# RPi-GPIO-V4.net
KiCad netlist of a schematic drawn in EAGLE
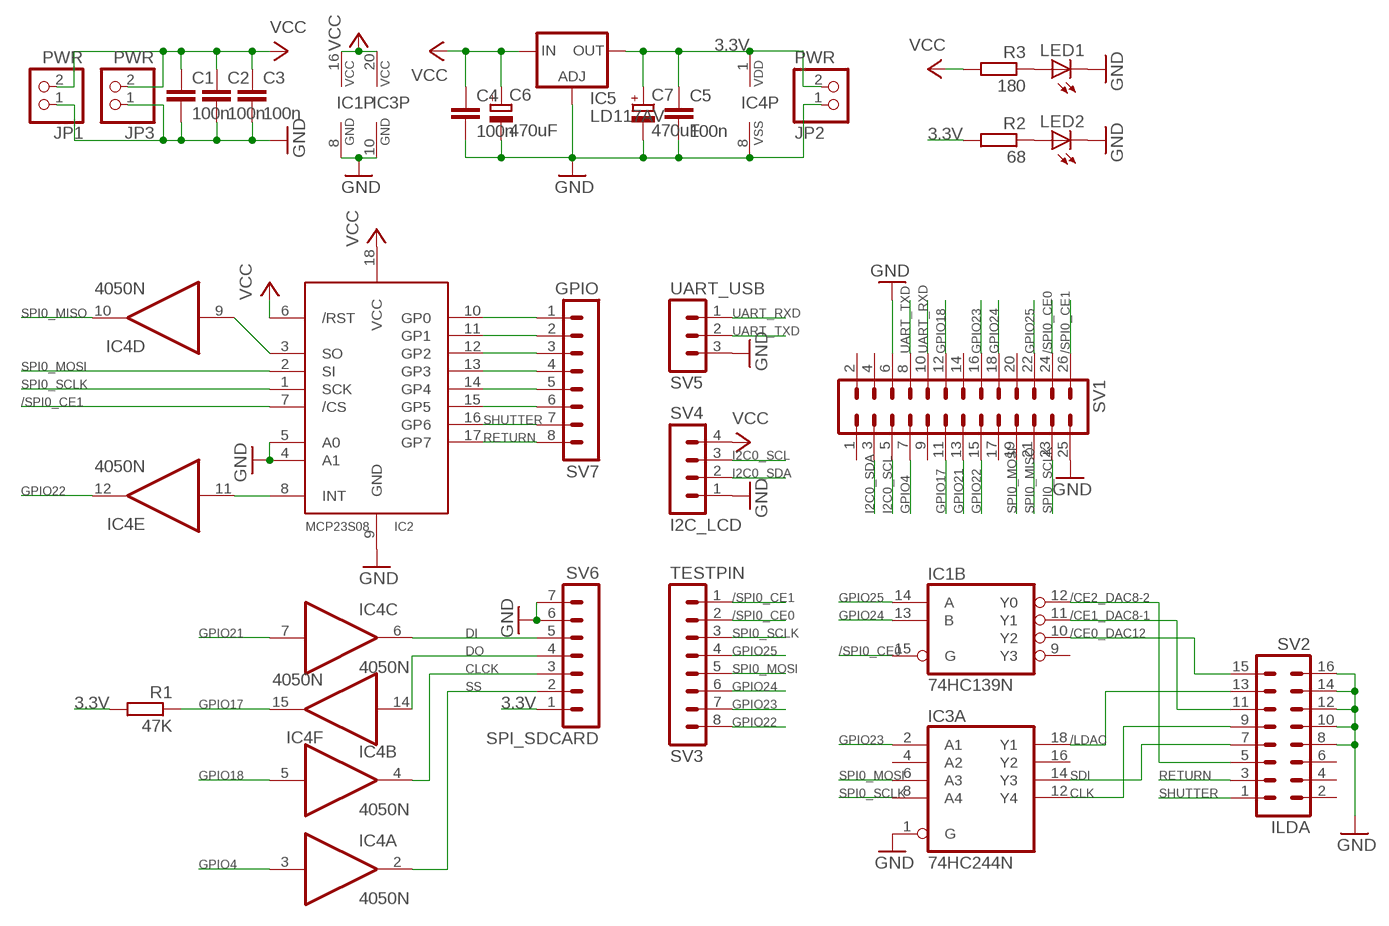
[diagram p0: schematic, sheet 1]

(export (version "E")
  (design (tool "Eeschema 10.0.6"))
  (components
    (comp (ref "C1")
      (value "100n")
      (footprint "eagle-import:C050-024X044")
      (libsource (lib "eagle-import") (part "C-EU050-024X044"))
    )
    (comp (ref "C2")
      (value "100n")
      (footprint "eagle-import:C050-024X044")
      (libsource (lib "eagle-import") (part "C-EU050-024X044"))
    )
    (comp (ref "C3")
      (value "100n")
      (footprint "eagle-import:C050-024X044")
      (libsource (lib "eagle-import") (part "C-EU050-024X044"))
    )
    (comp (ref "C4")
      (value "100n")
      (footprint "eagle-import:C050-024X044")
      (libsource (lib "eagle-import") (part "C-EU050-024X044"))
    )
    (comp (ref "C5")
      (value "100n")
      (footprint "eagle-import:C050-024X044")
      (libsource (lib "eagle-import") (part "C-EU050-024X044"))
    )
    (comp (ref "C6")
      (value "470uF")
      (footprint "eagle-import:E5-8,5")
      (libsource (lib "eagle-import") (part "CPOL-EUE5-8.5"))
    )
    (comp (ref "C7")
      (value "470uF")
      (footprint "eagle-import:E5-8,5")
      (libsource (lib "eagle-import") (part "CPOL-EUE5-8.5"))
    )
    (comp (ref "IC1")
      (value "74HC139N")
      (footprint "eagle-import:DIL16")
      (libsource (lib "eagle-import") (part "74139NHC"))
    )
    (comp (ref "IC2")
      (value "MCP2300X/P")
      (footprint "eagle-import:DIL18")
      (libsource (lib "eagle-import") (part "MCP2300X/P"))
    )
    (comp (ref "IC3")
      (value "74HC244N")
      (footprint "eagle-import:DIL20")
      (libsource (lib "eagle-import") (part "74244NHC"))
    )
    (comp (ref "IC4")
      (value "4050N")
      (footprint "eagle-import:DIL16")
      (libsource (lib "eagle-import") (part "4050N"))
    )
    (comp (ref "IC5")
      (value "LD117AV")
      (footprint "eagle-import:TO220L1")
      (libsource (lib "eagle-import") (part "LD117A?V"))
    )
    (comp (ref "JP1")
      (value "PWR")
      (footprint "eagle-import:1X02")
      (libsource (lib "eagle-import") (part "PINHD-1X2"))
    )
    (comp (ref "JP2")
      (value "PWR")
      (footprint "eagle-import:1X02")
      (libsource (lib "eagle-import") (part "PINHD-1X2"))
    )
    (comp (ref "JP3")
      (value "PWR")
      (footprint "eagle-import:1X02")
      (libsource (lib "eagle-import") (part "PINHD-1X2"))
    )
    (comp (ref "LED1")
      (value "LED3MM")
      (footprint "eagle-import:LED3MM")
      (libsource (lib "eagle-import") (part "LED3MM"))
    )
    (comp (ref "LED2")
      (value "LED3MM")
      (footprint "eagle-import:LED3MM")
      (libsource (lib "eagle-import") (part "LED3MM"))
    )
    (comp (ref "R1")
      (value "47K")
      (footprint "eagle-import:0204_5")
      (libsource (lib "eagle-import") (part "R-EU_0204/5"))
    )
    (comp (ref "R2")
      (value "68")
      (footprint "eagle-import:0204_5")
      (libsource (lib "eagle-import") (part "R-EU_0204/5"))
    )
    (comp (ref "R3")
      (value "180")
      (footprint "eagle-import:0204_5")
      (libsource (lib "eagle-import") (part "R-EU_0204/5"))
    )
    (comp (ref "SV1")
      (value "MA13-2")
      (footprint "eagle-import:MA13-2")
      (libsource (lib "eagle-import") (part "MA13-2"))
    )
    (comp (ref "SV2")
      (value "ILDA")
      (footprint "eagle-import:MA08-2")
      (libsource (lib "eagle-import") (part "MA08-2"))
    )
    (comp (ref "SV3")
      (value "TESTPIN")
      (footprint "eagle-import:MA08-1")
      (libsource (lib "eagle-import") (part "MA08-1"))
    )
    (comp (ref "SV4")
      (value "I2C_LCD")
      (footprint "eagle-import:MA04-1")
      (libsource (lib "eagle-import") (part "MA04-1"))
    )
    (comp (ref "SV5")
      (value "UART_USB")
      (footprint "eagle-import:MA03-1")
      (fields (field (name "OC_FARNELL") "unknown") (field (name "OC_NEWARK") "unknown"))
      (libsource (lib "eagle-import") (part "MA03-1"))
    )
    (comp (ref "SV6")
      (value "SPI_SDCARD")
      (footprint "eagle-import:MA07-1")
      (libsource (lib "eagle-import") (part "MA07-1"))
    )
    (comp (ref "SV7")
      (value "GPIO")
      (footprint "eagle-import:MA08-1")
      (fields (field (name "OC_FARNELL") "unknown") (field (name "OC_NEWARK") "unknown"))
      (libsource (lib "eagle-import") (part "MA08-1"))
    )
  )
  (nets
    (net (code "1") (name "/3.3V") (class "Default")
      (node (ref "C5") (pin "1") (pinfunction "1_1") (pintype "passive"))
      (node (ref "C7") (pin "+") (pinfunction "+_+") (pintype "passive"))
      (node (ref "IC4") (pin "1") (pinfunction "VDD_1") (pintype "power_in"))
      (node (ref "IC5") (pin "2") (pinfunction "OUT_2") (pintype "passive"))
      (node (ref "JP2") (pin "2") (pinfunction "2_2") (pintype "passive"))
      (node (ref "R1") (pin "2") (pinfunction "2_2") (pintype "passive"))
      (node (ref "R2") (pin "2") (pinfunction "2_2") (pintype "passive"))
      (node (ref "SV6") (pin "1") (pinfunction "1_1") (pintype "passive"))
    )
    (net (code "2") (name "/CLCK") (class "Default")
      (node (ref "IC4") (pin "4") (pinfunction "O_4") (pintype "output"))
      (node (ref "SV6") (pin "3") (pinfunction "3_3") (pintype "passive"))
    )
    (net (code "3") (name "/CLK") (class "Default")
      (node (ref "IC3") (pin "12") (pinfunction "Y4_12") (pintype "tri_state"))
      (node (ref "SV2") (pin "9") (pinfunction "9_9") (pintype "passive"))
    )
    (net (code "4") (name "/DI") (class "Default")
      (node (ref "IC4") (pin "6") (pinfunction "O_6") (pintype "output"))
      (node (ref "SV6") (pin "5") (pinfunction "5_5") (pintype "passive"))
    )
    (net (code "5") (name "/DO") (class "Default")
      (node (ref "IC4") (pin "14") (pinfunction "I_14") (pintype "input"))
      (node (ref "SV6") (pin "4") (pinfunction "4_4") (pintype "passive"))
    )
    (net (code "6") (name "/GPIO4") (class "Default")
      (node (ref "IC4") (pin "3") (pinfunction "I_3") (pintype "input"))
      (node (ref "SV1") (pin "7") (pinfunction "7_7") (pintype "passive"))
    )
    (net (code "7") (name "/GPIO17") (class "Default")
      (node (ref "IC4") (pin "15") (pinfunction "O_15") (pintype "output"))
      (node (ref "R1") (pin "1") (pinfunction "1_1") (pintype "passive"))
      (node (ref "SV1") (pin "11") (pinfunction "11_11") (pintype "passive"))
    )
    (net (code "8") (name "/GPIO18") (class "Default")
      (node (ref "IC4") (pin "5") (pinfunction "I_5") (pintype "input"))
      (node (ref "SV1") (pin "12") (pinfunction "12_12") (pintype "passive"))
    )
    (net (code "9") (name "/GPIO21") (class "Default")
      (node (ref "IC4") (pin "7") (pinfunction "I_7") (pintype "input"))
      (node (ref "SV1") (pin "13") (pinfunction "13_13") (pintype "passive"))
    )
    (net (code "10") (name "/GPIO22") (class "Default")
      (node (ref "IC4") (pin "12") (pinfunction "O_12") (pintype "output"))
      (node (ref "SV1") (pin "15") (pinfunction "15_15") (pintype "passive"))
      (node (ref "SV3") (pin "8") (pinfunction "8_8") (pintype "passive"))
    )
    (net (code "11") (name "/GPIO23") (class "Default")
      (node (ref "IC3") (pin "2") (pinfunction "A1_2") (pintype "input"))
      (node (ref "SV1") (pin "16") (pinfunction "16_16") (pintype "passive"))
      (node (ref "SV3") (pin "7") (pinfunction "7_7") (pintype "passive"))
    )
    (net (code "12") (name "/GPIO24") (class "Default")
      (node (ref "IC1") (pin "13") (pinfunction "B_13") (pintype "input"))
      (node (ref "SV1") (pin "18") (pinfunction "18_18") (pintype "passive"))
      (node (ref "SV3") (pin "6") (pinfunction "6_6") (pintype "passive"))
    )
    (net (code "13") (name "/GPIO25") (class "Default")
      (node (ref "IC1") (pin "14") (pinfunction "A_14") (pintype "input"))
      (node (ref "SV1") (pin "22") (pinfunction "22_22") (pintype "passive"))
      (node (ref "SV3") (pin "4") (pinfunction "4_4") (pintype "passive"))
    )
    (net (code "14") (name "/I2C0_SCL") (class "Default")
      (node (ref "SV1") (pin "5") (pinfunction "5_5") (pintype "passive"))
      (node (ref "SV4") (pin "3") (pinfunction "3_3") (pintype "passive"))
    )
    (net (code "15") (name "/I2C0_SDA") (class "Default")
      (node (ref "SV1") (pin "3") (pinfunction "3_3") (pintype "passive"))
      (node (ref "SV4") (pin "2") (pinfunction "2_2") (pintype "passive"))
    )
    (net (code "16") (name "/RETURN") (class "Default")
      (node (ref "IC2") (pin "17") (pinfunction "GP7_17") (pintype "bidirectional"))
      (node (ref "SV2") (pin "3") (pinfunction "3_3") (pintype "passive"))
      (node (ref "SV7") (pin "8") (pinfunction "8_8") (pintype "passive"))
    )
    (net (code "17") (name "/SDI") (class "Default")
      (node (ref "IC3") (pin "14") (pinfunction "Y3_14") (pintype "tri_state"))
      (node (ref "SV2") (pin "7") (pinfunction "7_7") (pintype "passive"))
    )
    (net (code "18") (name "/SHUTTER") (class "Default")
      (node (ref "IC2") (pin "16") (pinfunction "GP6_16") (pintype "bidirectional"))
      (node (ref "SV2") (pin "1") (pinfunction "1_1") (pintype "passive"))
      (node (ref "SV7") (pin "7") (pinfunction "7_7") (pintype "passive"))
    )
    (net (code "19") (name "/SPI0_MISO") (class "Default")
      (node (ref "IC4") (pin "10") (pinfunction "O_10") (pintype "output"))
      (node (ref "SV1") (pin "21") (pinfunction "21_21") (pintype "passive"))
    )
    (net (code "20") (name "/SPI0_MOSI") (class "Default")
      (node (ref "IC2") (pin "2") (pinfunction "SI_2") (pintype "bidirectional"))
      (node (ref "IC3") (pin "6") (pinfunction "A3_6") (pintype "input"))
      (node (ref "SV1") (pin "19") (pinfunction "19_19") (pintype "passive"))
      (node (ref "SV3") (pin "5") (pinfunction "5_5") (pintype "passive"))
    )
    (net (code "21") (name "/SPI0_SCLK") (class "Default")
      (node (ref "IC2") (pin "1") (pinfunction "SCK_1") (pintype "bidirectional"))
      (node (ref "IC3") (pin "8") (pinfunction "A4_8") (pintype "input"))
      (node (ref "SV1") (pin "23") (pinfunction "23_23") (pintype "passive"))
      (node (ref "SV3") (pin "3") (pinfunction "3_3") (pintype "passive"))
    )
    (net (code "22") (name "/SS") (class "Default")
      (node (ref "IC4") (pin "2") (pinfunction "O_2") (pintype "output"))
      (node (ref "SV6") (pin "2") (pinfunction "2_2") (pintype "passive"))
    )
    (net (code "23") (name "/UART_RXD") (class "Default")
      (node (ref "SV1") (pin "10") (pinfunction "10_10") (pintype "passive"))
      (node (ref "SV5") (pin "1") (pinfunction "1_1") (pintype "passive"))
    )
    (net (code "24") (name "/UART_TXD") (class "Default")
      (node (ref "SV1") (pin "8") (pinfunction "8_8") (pintype "passive"))
      (node (ref "SV5") (pin "2") (pinfunction "2_2") (pintype "passive"))
    )
    (net (code "25") (name "/{slash}CE0_DAC12") (class "Default")
      (node (ref "IC1") (pin "10") (pinfunction "Y2_10") (pintype "output"))
      (node (ref "SV2") (pin "15") (pinfunction "15_15") (pintype "passive"))
    )
    (net (code "26") (name "/{slash}CE1_DAC8-1") (class "Default")
      (node (ref "IC1") (pin "11") (pinfunction "Y1_11") (pintype "output"))
      (node (ref "SV2") (pin "11") (pinfunction "11_11") (pintype "passive"))
    )
    (net (code "27") (name "/{slash}CE2_DAC8-2") (class "Default")
      (node (ref "IC1") (pin "12") (pinfunction "Y0_12") (pintype "output"))
      (node (ref "SV2") (pin "5") (pinfunction "5_5") (pintype "passive"))
    )
    (net (code "28") (name "/{slash}LDAC") (class "Default")
      (node (ref "IC3") (pin "18") (pinfunction "Y1_18") (pintype "tri_state"))
      (node (ref "SV2") (pin "13") (pinfunction "13_13") (pintype "passive"))
    )
    (net (code "29") (name "/{slash}SPI0_CE0") (class "Default")
      (node (ref "IC1") (pin "15") (pinfunction "G_15") (pintype "input"))
      (node (ref "SV1") (pin "24") (pinfunction "24_24") (pintype "passive"))
      (node (ref "SV3") (pin "2") (pinfunction "2_2") (pintype "passive"))
    )
    (net (code "30") (name "/{slash}SPI0_CE1") (class "Default")
      (node (ref "IC2") (pin "7") (pinfunction "/CS_7") (pintype "input"))
      (node (ref "SV1") (pin "26") (pinfunction "26_26") (pintype "passive"))
      (node (ref "SV3") (pin "1") (pinfunction "1_1") (pintype "passive"))
    )
    (net (code "31") (name "GND") (class "Default")
      (node (ref "C1") (pin "2") (pinfunction "2_2") (pintype "passive"))
      (node (ref "C2") (pin "2") (pinfunction "2_2") (pintype "passive"))
      (node (ref "C3") (pin "2") (pinfunction "2_2") (pintype "passive"))
      (node (ref "C4") (pin "2") (pinfunction "2_2") (pintype "passive"))
      (node (ref "C5") (pin "2") (pinfunction "2_2") (pintype "passive"))
      (node (ref "C6") (pin "-") (pinfunction "-_-") (pintype "passive"))
      (node (ref "C7") (pin "-") (pinfunction "-_-") (pintype "passive"))
      (node (ref "IC1") (pin "8") (pinfunction "GND_8") (pintype "power_in"))
      (node (ref "IC2") (pin "4") (pinfunction "A1_4") (pintype "input"))
      (node (ref "IC2") (pin "5") (pinfunction "A0_5") (pintype "input"))
      (node (ref "IC2") (pin "9") (pinfunction "GND_9") (pintype "power_in"))
      (node (ref "IC3") (pin "1") (pinfunction "G_1") (pintype "input"))
      (node (ref "IC3") (pin "10") (pinfunction "GND_10") (pintype "power_in"))
      (node (ref "IC4") (pin "8") (pinfunction "VSS_8") (pintype "power_in"))
      (node (ref "IC5") (pin "1") (pinfunction "ADJ_1") (pintype "input"))
      (node (ref "JP1") (pin "1") (pinfunction "1_1") (pintype "passive"))
      (node (ref "JP2") (pin "1") (pinfunction "1_1") (pintype "passive"))
      (node (ref "JP3") (pin "1") (pinfunction "1_1") (pintype "passive"))
      (node (ref "LED1") (pin "K") (pinfunction "C_K") (pintype "passive"))
      (node (ref "LED2") (pin "K") (pinfunction "C_K") (pintype "passive"))
      (node (ref "SV1") (pin "25") (pinfunction "25_25") (pintype "passive"))
      (node (ref "SV1") (pin "6") (pinfunction "6_6") (pintype "passive"))
      (node (ref "SV2") (pin "10") (pinfunction "10_10") (pintype "passive"))
      (node (ref "SV2") (pin "12") (pinfunction "12_12") (pintype "passive"))
      (node (ref "SV2") (pin "14") (pinfunction "14_14") (pintype "passive"))
      (node (ref "SV2") (pin "16") (pinfunction "16_16") (pintype "passive"))
      (node (ref "SV2") (pin "8") (pinfunction "8_8") (pintype "passive"))
      (node (ref "SV4") (pin "1") (pinfunction "1_1") (pintype "passive"))
      (node (ref "SV5") (pin "3") (pinfunction "3_3") (pintype "passive"))
      (node (ref "SV6") (pin "6") (pinfunction "6_6") (pintype "passive"))
      (node (ref "SV6") (pin "7") (pinfunction "7_7") (pintype "passive"))
    )
    (net (code "32") (name "Net-(IC2-GP0)") (class "Default")
      (node (ref "IC2") (pin "10") (pinfunction "GP0_10") (pintype "bidirectional"))
      (node (ref "SV7") (pin "1") (pinfunction "1_1") (pintype "passive"))
    )
    (net (code "33") (name "Net-(IC2-GP1)") (class "Default")
      (node (ref "IC2") (pin "11") (pinfunction "GP1_11") (pintype "bidirectional"))
      (node (ref "SV7") (pin "2") (pinfunction "2_2") (pintype "passive"))
    )
    (net (code "34") (name "Net-(IC2-GP2)") (class "Default")
      (node (ref "IC2") (pin "12") (pinfunction "GP2_12") (pintype "bidirectional"))
      (node (ref "SV7") (pin "3") (pinfunction "3_3") (pintype "passive"))
    )
    (net (code "35") (name "Net-(IC2-GP3)") (class "Default")
      (node (ref "IC2") (pin "13") (pinfunction "GP3_13") (pintype "bidirectional"))
      (node (ref "SV7") (pin "4") (pinfunction "4_4") (pintype "passive"))
    )
    (net (code "36") (name "Net-(IC2-GP4)") (class "Default")
      (node (ref "IC2") (pin "14") (pinfunction "GP4_14") (pintype "bidirectional"))
      (node (ref "SV7") (pin "5") (pinfunction "5_5") (pintype "passive"))
    )
    (net (code "37") (name "Net-(IC2-GP5)") (class "Default")
      (node (ref "IC2") (pin "15") (pinfunction "GP5_15") (pintype "bidirectional"))
      (node (ref "SV7") (pin "6") (pinfunction "6_6") (pintype "passive"))
    )
    (net (code "38") (name "Net-(IC2-INT)") (class "Default")
      (node (ref "IC2") (pin "8") (pinfunction "INT_8") (pintype "output"))
      (node (ref "IC4") (pin "11") (pinfunction "I_11") (pintype "input"))
    )
    (net (code "39") (name "Net-(IC2-SO)") (class "Default")
      (node (ref "IC2") (pin "3") (pinfunction "SO_3") (pintype "output"))
      (node (ref "IC4") (pin "9") (pinfunction "I_9") (pintype "input"))
    )
    (net (code "40") (name "Net-(LED1-PadA)") (class "Default")
      (node (ref "LED1") (pin "A") (pinfunction "A_A") (pintype "passive"))
      (node (ref "R3") (pin "1") (pinfunction "1_1") (pintype "passive"))
    )
    (net (code "41") (name "Net-(LED2-PadA)") (class "Default")
      (node (ref "LED2") (pin "A") (pinfunction "A_A") (pintype "passive"))
      (node (ref "R2") (pin "1") (pinfunction "1_1") (pintype "passive"))
    )
    (net (code "42") (name "VCC") (class "Default")
      (node (ref "C1") (pin "1") (pinfunction "1_1") (pintype "passive"))
      (node (ref "C2") (pin "1") (pinfunction "1_1") (pintype "passive"))
      (node (ref "C3") (pin "1") (pinfunction "1_1") (pintype "passive"))
      (node (ref "C4") (pin "1") (pinfunction "1_1") (pintype "passive"))
      (node (ref "C6") (pin "+") (pinfunction "+_+") (pintype "passive"))
      (node (ref "IC1") (pin "16") (pinfunction "VCC_16") (pintype "power_in"))
      (node (ref "IC2") (pin "18") (pinfunction "VCC_18") (pintype "power_in"))
      (node (ref "IC2") (pin "6") (pinfunction "/RST_6") (pintype "input"))
      (node (ref "IC3") (pin "20") (pinfunction "VCC_20") (pintype "power_in"))
      (node (ref "IC5") (pin "3") (pinfunction "IN_3") (pintype "input"))
      (node (ref "JP1") (pin "2") (pinfunction "2_2") (pintype "passive"))
      (node (ref "JP3") (pin "2") (pinfunction "2_2") (pintype "passive"))
      (node (ref "R3") (pin "2") (pinfunction "2_2") (pintype "passive"))
      (node (ref "SV4") (pin "4") (pinfunction "4_4") (pintype "passive"))
    )
    (net (code "43") (name "unconnected-(IC1B-Y3-Pad9)") (class "Default")
      (node (ref "IC1") (pin "9") (pinfunction "Y3_9") (pintype "output"))
    )
    (net (code "44") (name "unconnected-(IC3A-A2-Pad4)") (class "Default")
      (node (ref "IC3") (pin "4") (pinfunction "A2_4") (pintype "input"))
    )
    (net (code "45") (name "unconnected-(IC3A-Y2-Pad16)") (class "Default")
      (node (ref "IC3") (pin "16") (pinfunction "Y2_16") (pintype "tri_state"))
    )
    (net (code "46") (name "unconnected-(SV1-Pad1)") (class "Default")
      (node (ref "SV1") (pin "1") (pinfunction "1_1") (pintype "passive"))
    )
    (net (code "47") (name "unconnected-(SV1-Pad2)") (class "Default")
      (node (ref "SV1") (pin "2") (pinfunction "2_2") (pintype "passive"))
    )
    (net (code "48") (name "unconnected-(SV1-Pad4)") (class "Default")
      (node (ref "SV1") (pin "4") (pinfunction "4_4") (pintype "passive"))
    )
    (net (code "49") (name "unconnected-(SV1-Pad9)") (class "Default")
      (node (ref "SV1") (pin "9") (pinfunction "9_9") (pintype "passive"))
    )
    (net (code "50") (name "unconnected-(SV1-Pad14)") (class "Default")
      (node (ref "SV1") (pin "14") (pinfunction "14_14") (pintype "passive"))
    )
    (net (code "51") (name "unconnected-(SV1-Pad17)") (class "Default")
      (node (ref "SV1") (pin "17") (pinfunction "17_17") (pintype "passive"))
    )
    (net (code "52") (name "unconnected-(SV1-Pad20)") (class "Default")
      (node (ref "SV1") (pin "20") (pinfunction "20_20") (pintype "passive"))
    )
    (net (code "53") (name "unconnected-(SV2-Pad2)") (class "Default")
      (node (ref "SV2") (pin "2") (pinfunction "2_2") (pintype "passive"))
    )
    (net (code "54") (name "unconnected-(SV2-Pad4)") (class "Default")
      (node (ref "SV2") (pin "4") (pinfunction "4_4") (pintype "passive"))
    )
    (net (code "55") (name "unconnected-(SV2-Pad6)") (class "Default")
      (node (ref "SV2") (pin "6") (pinfunction "6_6") (pintype "passive"))
    )
  )
)
